# Prototype1.net
KiCad netlist of a schematic drawn in EAGLE
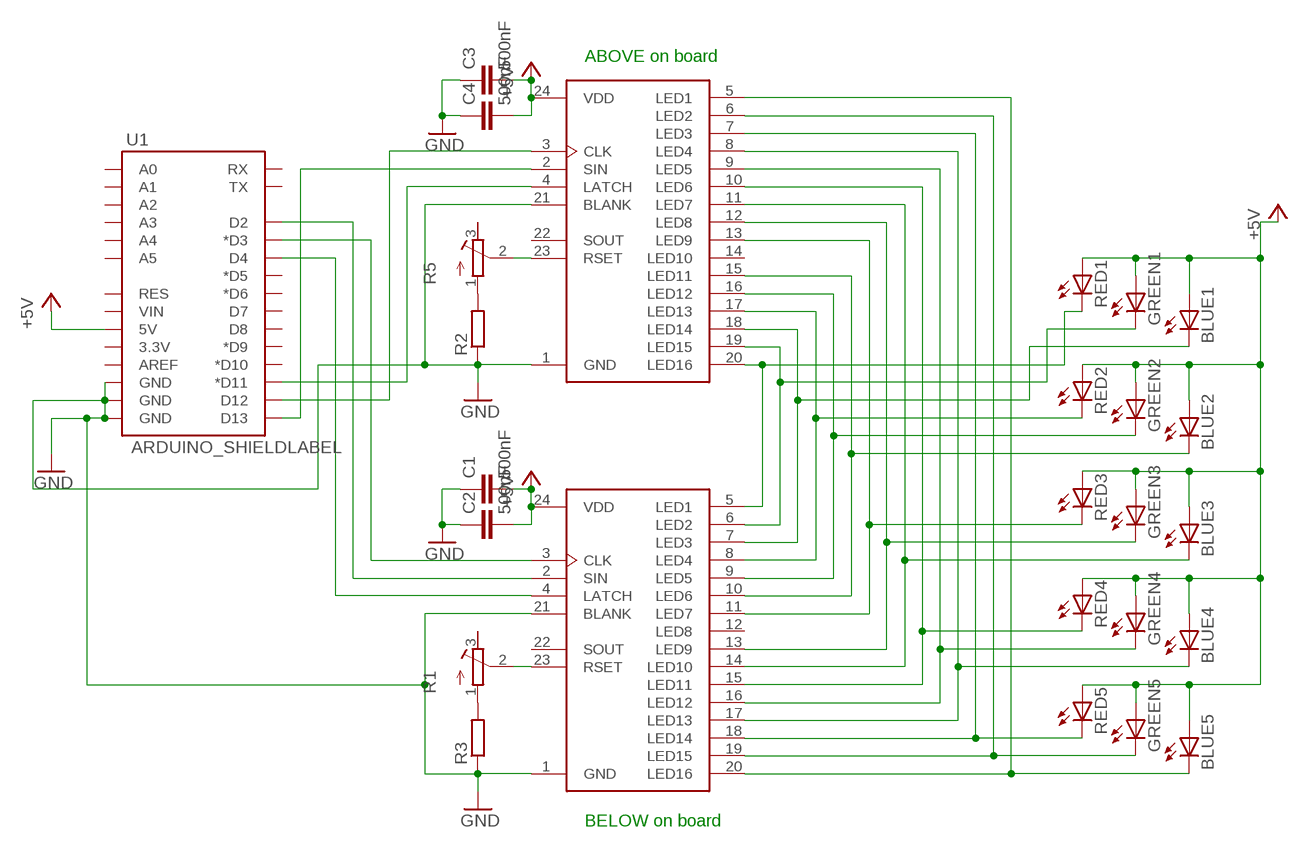
[diagram p0: schematic, sheet 1]

(export (version "E")
  (design (tool "Eeschema 10.0.6"))
  (components
    (comp (ref "BLUE1")
      (value "LEDKA-3528ASYC")
      (footprint "eagle-import:KA-3528ASYC")
      (libsource (lib "eagle-import") (part "LEDKA-3528ASYC"))
    )
    (comp (ref "BLUE2")
      (value "LEDKA-3528ASYC")
      (footprint "eagle-import:KA-3528ASYC")
      (libsource (lib "eagle-import") (part "LEDKA-3528ASYC"))
    )
    (comp (ref "BLUE3")
      (value "LEDKA-3528ASYC")
      (footprint "eagle-import:KA-3528ASYC")
      (libsource (lib "eagle-import") (part "LEDKA-3528ASYC"))
    )
    (comp (ref "BLUE4")
      (value "LEDKA-3528ASYC")
      (footprint "eagle-import:KA-3528ASYC")
      (libsource (lib "eagle-import") (part "LEDKA-3528ASYC"))
    )
    (comp (ref "BLUE5")
      (value "LEDKA-3528ASYC")
      (footprint "eagle-import:KA-3528ASYC")
      (libsource (lib "eagle-import") (part "LEDKA-3528ASYC"))
    )
    (comp (ref "C1")
      (value "500nF")
      (footprint "eagle-import:CAP-PTH-SMALL")
      (libsource (lib "eagle-import") (part "CAPPTH"))
    )
    (comp (ref "C2")
      (value "500nF")
      (footprint "eagle-import:CAP-PTH-SMALL")
      (libsource (lib "eagle-import") (part "CAPPTH"))
    )
    (comp (ref "C3")
      (value "500nF")
      (footprint "eagle-import:CAP-PTH-SMALL")
      (libsource (lib "eagle-import") (part "CAPPTH"))
    )
    (comp (ref "C4")
      (value "500nF")
      (footprint "eagle-import:CAP-PTH-SMALL")
      (libsource (lib "eagle-import") (part "CAPPTH"))
    )
    (comp (ref "GREEN1")
      (value "LEDKA-3528ASYC")
      (footprint "eagle-import:KA-3528ASYC")
      (libsource (lib "eagle-import") (part "LEDKA-3528ASYC"))
    )
    (comp (ref "GREEN2")
      (value "LEDKA-3528ASYC")
      (footprint "eagle-import:KA-3528ASYC")
      (libsource (lib "eagle-import") (part "LEDKA-3528ASYC"))
    )
    (comp (ref "GREEN3")
      (value "LEDKA-3528ASYC")
      (footprint "eagle-import:KA-3528ASYC")
      (libsource (lib "eagle-import") (part "LEDKA-3528ASYC"))
    )
    (comp (ref "GREEN4")
      (value "LEDKA-3528ASYC")
      (footprint "eagle-import:KA-3528ASYC")
      (libsource (lib "eagle-import") (part "LEDKA-3528ASYC"))
    )
    (comp (ref "GREEN5")
      (value "LEDKA-3528ASYC")
      (footprint "eagle-import:KA-3528ASYC")
      (libsource (lib "eagle-import") (part "LEDKA-3528ASYC"))
    )
    (comp (ref "R1")
      (value "R-TRIMM3165W")
      (footprint "eagle-import:RTRIM3165W")
      (libsource (lib "eagle-import") (part "R-TRIMM3165W"))
    )
    (comp (ref "R2")
      (value "R-EU_0204/7")
      (footprint "eagle-import:0204_7")
      (libsource (lib "eagle-import") (part "R-EU_0204/7"))
    )
    (comp (ref "R3")
      (value "R-EU_0204/7")
      (footprint "eagle-import:0204_7")
      (libsource (lib "eagle-import") (part "R-EU_0204/7"))
    )
    (comp (ref "R5")
      (value "R-TRIMM3165W")
      (footprint "eagle-import:RTRIM3165W")
      (libsource (lib "eagle-import") (part "R-TRIMM3165W"))
    )
    (comp (ref "RED1")
      (value "LEDSML0805")
      (footprint "eagle-import:SML0805")
      (libsource (lib "eagle-import") (part "LEDSML0805"))
    )
    (comp (ref "RED2")
      (value "LEDSML0805")
      (footprint "eagle-import:SML0805")
      (libsource (lib "eagle-import") (part "LEDSML0805"))
    )
    (comp (ref "RED3")
      (value "LEDSML0805")
      (footprint "eagle-import:SML0805")
      (libsource (lib "eagle-import") (part "LEDSML0805"))
    )
    (comp (ref "RED4")
      (value "LEDSML0805")
      (footprint "eagle-import:SML0805")
      (libsource (lib "eagle-import") (part "LEDSML0805"))
    )
    (comp (ref "RED5")
      (value "LEDSML0805")
      (footprint "eagle-import:SML0805")
      (libsource (lib "eagle-import") (part "LEDSML0805"))
    )
    (comp (ref "U$2")
      (value "CAT4016")
      (footprint "eagle-import:SOIC24W")
      (libsource (lib "eagle-import") (part "CAT4016"))
    )
    (comp (ref "U$3")
      (value "CAT4016")
      (footprint "eagle-import:SOIC24W")
      (libsource (lib "eagle-import") (part "CAT4016"))
    )
    (comp (ref "U1")
      (value "ARDUINO_SHIELDLABEL")
      (footprint "eagle-import:DUEMILANOVE_SHIELD")
      (libsource (lib "eagle-import") (part "ARDUINO_SHIELDLABEL"))
    )
  )
  (nets
    (net (code "1") (name "+5V") (class "Default")
      (node (ref "BLUE1") (pin "A") (pinfunction "A_A") (pintype "passive"))
      (node (ref "BLUE2") (pin "A") (pinfunction "A_A") (pintype "passive"))
      (node (ref "BLUE3") (pin "A") (pinfunction "A_A") (pintype "passive"))
      (node (ref "BLUE4") (pin "A") (pinfunction "A_A") (pintype "passive"))
      (node (ref "BLUE5") (pin "A") (pinfunction "A_A") (pintype "passive"))
      (node (ref "C1") (pin "2") (pinfunction "2_2") (pintype "passive"))
      (node (ref "C2") (pin "2") (pinfunction "2_2") (pintype "passive"))
      (node (ref "C3") (pin "2") (pinfunction "2_2") (pintype "passive"))
      (node (ref "C4") (pin "2") (pinfunction "2_2") (pintype "passive"))
      (node (ref "GREEN1") (pin "A") (pinfunction "A_A") (pintype "passive"))
      (node (ref "GREEN2") (pin "A") (pinfunction "A_A") (pintype "passive"))
      (node (ref "GREEN3") (pin "A") (pinfunction "A_A") (pintype "passive"))
      (node (ref "GREEN4") (pin "A") (pinfunction "A_A") (pintype "passive"))
      (node (ref "GREEN5") (pin "A") (pinfunction "A_A") (pintype "passive"))
      (node (ref "RED1") (pin "A") (pinfunction "A_A") (pintype "passive"))
      (node (ref "RED2") (pin "A") (pinfunction "A_A") (pintype "passive"))
      (node (ref "RED3") (pin "A") (pinfunction "A_A") (pintype "passive"))
      (node (ref "RED4") (pin "A") (pinfunction "A_A") (pintype "passive"))
      (node (ref "RED5") (pin "A") (pinfunction "A_A") (pintype "passive"))
      (node (ref "U$2") (pin "24") (pinfunction "VDD_24") (pintype "bidirectional"))
      (node (ref "U$3") (pin "24") (pinfunction "VDD_24") (pintype "bidirectional"))
      (node (ref "U1") (pin "5V") (pinfunction "5V_5V") (pintype "bidirectional"))
    )
    (net (code "2") (name "GND") (class "Default")
      (node (ref "C1") (pin "1") (pinfunction "1_1") (pintype "passive"))
      (node (ref "C2") (pin "1") (pinfunction "1_1") (pintype "passive"))
      (node (ref "C3") (pin "1") (pinfunction "1_1") (pintype "passive"))
      (node (ref "C4") (pin "1") (pinfunction "1_1") (pintype "passive"))
      (node (ref "R2") (pin "1") (pinfunction "1_1") (pintype "passive"))
      (node (ref "R3") (pin "1") (pinfunction "1_1") (pintype "passive"))
      (node (ref "U$2") (pin "1") (pinfunction "GND_1") (pintype "bidirectional"))
      (node (ref "U$2") (pin "21") (pinfunction "BLANK_21") (pintype "bidirectional"))
      (node (ref "U$3") (pin "1") (pinfunction "GND_1") (pintype "bidirectional"))
      (node (ref "U$3") (pin "21") (pinfunction "BLANK_21") (pintype "bidirectional"))
      (node (ref "U1") (pin "GND@0") (pinfunction "GND_GND@0") (pintype "bidirectional"))
      (node (ref "U1") (pin "GND@1") (pinfunction "GND_GND@1") (pintype "bidirectional"))
      (node (ref "U1") (pin "GND@2") (pinfunction "GND_GND@2") (pintype "bidirectional"))
    )
    (net (code "3") (name "Net-(R1-A)") (class "Default")
      (node (ref "R1") (pin "1") (pinfunction "A_1") (pintype "passive"))
      (node (ref "R3") (pin "2") (pinfunction "2_2") (pintype "passive"))
    )
    (net (code "4") (name "Net-(R1-S)") (class "Default")
      (node (ref "R1") (pin "2") (pinfunction "S_2") (pintype "passive"))
      (node (ref "U$2") (pin "23") (pinfunction "RSET_23") (pintype "bidirectional"))
    )
    (net (code "5") (name "Net-(R5-A)") (class "Default")
      (node (ref "R2") (pin "2") (pinfunction "2_2") (pintype "passive"))
      (node (ref "R5") (pin "1") (pinfunction "A_1") (pintype "passive"))
    )
    (net (code "6") (name "Net-(R5-S)") (class "Default")
      (node (ref "R5") (pin "2") (pinfunction "S_2") (pintype "passive"))
      (node (ref "U$3") (pin "23") (pinfunction "RSET_23") (pintype "bidirectional"))
    )
    (net (code "7") (name "Net-(U$2-CLK)") (class "Default")
      (node (ref "U$2") (pin "3") (pinfunction "CLK_3") (pintype "bidirectional"))
      (node (ref "U1") (pin "D3") (pinfunction "*D3_D3") (pintype "bidirectional"))
    )
    (net (code "8") (name "Net-(U$2-LATCH)") (class "Default")
      (node (ref "U$2") (pin "4") (pinfunction "LATCH_4") (pintype "bidirectional"))
      (node (ref "U1") (pin "D4") (pinfunction "D4_D4") (pintype "bidirectional"))
    )
    (net (code "9") (name "Net-(U$2-LED1)") (class "Default")
      (node (ref "RED1") (pin "C") (pinfunction "C_C") (pintype "passive"))
      (node (ref "U$2") (pin "5") (pinfunction "LED1_5") (pintype "bidirectional"))
      (node (ref "U$3") (pin "20") (pinfunction "LED16_20") (pintype "bidirectional"))
    )
    (net (code "10") (name "Net-(U$2-LED2)") (class "Default")
      (node (ref "GREEN1") (pin "C") (pinfunction "C_C") (pintype "passive"))
      (node (ref "U$2") (pin "6") (pinfunction "LED2_6") (pintype "bidirectional"))
      (node (ref "U$3") (pin "19") (pinfunction "LED15_19") (pintype "bidirectional"))
    )
    (net (code "11") (name "Net-(U$2-LED3)") (class "Default")
      (node (ref "BLUE1") (pin "C") (pinfunction "C_C") (pintype "passive"))
      (node (ref "U$2") (pin "7") (pinfunction "LED3_7") (pintype "bidirectional"))
      (node (ref "U$3") (pin "18") (pinfunction "LED14_18") (pintype "bidirectional"))
    )
    (net (code "12") (name "Net-(U$2-LED4)") (class "Default")
      (node (ref "RED2") (pin "C") (pinfunction "C_C") (pintype "passive"))
      (node (ref "U$2") (pin "8") (pinfunction "LED4_8") (pintype "bidirectional"))
      (node (ref "U$3") (pin "17") (pinfunction "LED13_17") (pintype "bidirectional"))
    )
    (net (code "13") (name "Net-(U$2-LED5)") (class "Default")
      (node (ref "GREEN2") (pin "C") (pinfunction "C_C") (pintype "passive"))
      (node (ref "U$2") (pin "9") (pinfunction "LED5_9") (pintype "bidirectional"))
      (node (ref "U$3") (pin "16") (pinfunction "LED12_16") (pintype "bidirectional"))
    )
    (net (code "14") (name "Net-(U$2-LED6)") (class "Default")
      (node (ref "BLUE2") (pin "C") (pinfunction "C_C") (pintype "passive"))
      (node (ref "U$2") (pin "10") (pinfunction "LED6_10") (pintype "bidirectional"))
      (node (ref "U$3") (pin "15") (pinfunction "LED11_15") (pintype "bidirectional"))
    )
    (net (code "15") (name "Net-(U$2-LED7)") (class "Default")
      (node (ref "RED3") (pin "C") (pinfunction "C_C") (pintype "passive"))
      (node (ref "U$2") (pin "11") (pinfunction "LED7_11") (pintype "bidirectional"))
      (node (ref "U$3") (pin "13") (pinfunction "LED9_13") (pintype "bidirectional"))
    )
    (net (code "16") (name "Net-(U$2-LED9)") (class "Default")
      (node (ref "GREEN3") (pin "C") (pinfunction "C_C") (pintype "passive"))
      (node (ref "U$2") (pin "13") (pinfunction "LED9_13") (pintype "bidirectional"))
      (node (ref "U$3") (pin "12") (pinfunction "LED8_12") (pintype "bidirectional"))
    )
    (net (code "17") (name "Net-(U$2-LED10)") (class "Default")
      (node (ref "BLUE3") (pin "C") (pinfunction "C_C") (pintype "passive"))
      (node (ref "U$2") (pin "14") (pinfunction "LED10_14") (pintype "bidirectional"))
      (node (ref "U$3") (pin "11") (pinfunction "LED7_11") (pintype "bidirectional"))
    )
    (net (code "18") (name "Net-(U$2-LED11)") (class "Default")
      (node (ref "RED4") (pin "C") (pinfunction "C_C") (pintype "passive"))
      (node (ref "U$2") (pin "15") (pinfunction "LED11_15") (pintype "bidirectional"))
      (node (ref "U$3") (pin "10") (pinfunction "LED6_10") (pintype "bidirectional"))
    )
    (net (code "19") (name "Net-(U$2-LED12)") (class "Default")
      (node (ref "GREEN4") (pin "C") (pinfunction "C_C") (pintype "passive"))
      (node (ref "U$2") (pin "16") (pinfunction "LED12_16") (pintype "bidirectional"))
      (node (ref "U$3") (pin "9") (pinfunction "LED5_9") (pintype "bidirectional"))
    )
    (net (code "20") (name "Net-(U$2-LED13)") (class "Default")
      (node (ref "BLUE4") (pin "C") (pinfunction "C_C") (pintype "passive"))
      (node (ref "U$2") (pin "17") (pinfunction "LED13_17") (pintype "bidirectional"))
      (node (ref "U$3") (pin "8") (pinfunction "LED4_8") (pintype "bidirectional"))
    )
    (net (code "21") (name "Net-(U$2-LED14)") (class "Default")
      (node (ref "RED5") (pin "C") (pinfunction "C_C") (pintype "passive"))
      (node (ref "U$2") (pin "18") (pinfunction "LED14_18") (pintype "bidirectional"))
      (node (ref "U$3") (pin "7") (pinfunction "LED3_7") (pintype "bidirectional"))
    )
    (net (code "22") (name "Net-(U$2-LED15)") (class "Default")
      (node (ref "GREEN5") (pin "C") (pinfunction "C_C") (pintype "passive"))
      (node (ref "U$2") (pin "19") (pinfunction "LED15_19") (pintype "bidirectional"))
      (node (ref "U$3") (pin "6") (pinfunction "LED2_6") (pintype "bidirectional"))
    )
    (net (code "23") (name "Net-(U$2-LED16)") (class "Default")
      (node (ref "BLUE5") (pin "C") (pinfunction "C_C") (pintype "passive"))
      (node (ref "U$2") (pin "20") (pinfunction "LED16_20") (pintype "bidirectional"))
      (node (ref "U$3") (pin "5") (pinfunction "LED1_5") (pintype "bidirectional"))
    )
    (net (code "24") (name "Net-(U$2-SIN)") (class "Default")
      (node (ref "U$2") (pin "2") (pinfunction "SIN_2") (pintype "bidirectional"))
      (node (ref "U1") (pin "D2") (pinfunction "D2_D2") (pintype "bidirectional"))
    )
    (net (code "25") (name "Net-(U$3-CLK)") (class "Default")
      (node (ref "U$3") (pin "3") (pinfunction "CLK_3") (pintype "bidirectional"))
      (node (ref "U1") (pin "D12") (pinfunction "D12_D12") (pintype "bidirectional"))
    )
    (net (code "26") (name "Net-(U$3-LATCH)") (class "Default")
      (node (ref "U$3") (pin "4") (pinfunction "LATCH_4") (pintype "bidirectional"))
      (node (ref "U1") (pin "D11") (pinfunction "*D11_D11") (pintype "bidirectional"))
    )
    (net (code "27") (name "Net-(U$3-SIN)") (class "Default")
      (node (ref "U$3") (pin "2") (pinfunction "SIN_2") (pintype "bidirectional"))
      (node (ref "U1") (pin "D13") (pinfunction "D13_D13") (pintype "bidirectional"))
    )
    (net (code "28") (name "unconnected-(R1-E-Pad3)") (class "Default")
      (node (ref "R1") (pin "3") (pinfunction "E_3") (pintype "passive"))
    )
    (net (code "29") (name "unconnected-(R5-E-Pad3)") (class "Default")
      (node (ref "R5") (pin "3") (pinfunction "E_3") (pintype "passive"))
    )
    (net (code "30") (name "unconnected-(U$2-LED8-Pad12)") (class "Default")
      (node (ref "U$2") (pin "12") (pinfunction "LED8_12") (pintype "bidirectional"))
    )
    (net (code "31") (name "unconnected-(U$2-SOUT-Pad22)") (class "Default")
      (node (ref "U$2") (pin "22") (pinfunction "SOUT_22") (pintype "bidirectional"))
    )
    (net (code "32") (name "unconnected-(U$3-LED10-Pad14)") (class "Default")
      (node (ref "U$3") (pin "14") (pinfunction "LED10_14") (pintype "bidirectional"))
    )
    (net (code "33") (name "unconnected-(U$3-SOUT-Pad22)") (class "Default")
      (node (ref "U$3") (pin "22") (pinfunction "SOUT_22") (pintype "bidirectional"))
    )
    (net (code "34") (name "unconnected-(U1-*D5-PadD5)") (class "Default")
      (node (ref "U1") (pin "D5") (pinfunction "*D5_D5") (pintype "bidirectional"))
    )
    (net (code "35") (name "unconnected-(U1-*D6-PadD6)") (class "Default")
      (node (ref "U1") (pin "D6") (pinfunction "*D6_D6") (pintype "bidirectional"))
    )
    (net (code "36") (name "unconnected-(U1-*D9-PadD9)") (class "Default")
      (node (ref "U1") (pin "D9") (pinfunction "*D9_D9") (pintype "bidirectional"))
    )
    (net (code "37") (name "unconnected-(U1-*D10-PadD10)") (class "Default")
      (node (ref "U1") (pin "D10") (pinfunction "*D10_D10") (pintype "bidirectional"))
    )
    (net (code "38") (name "unconnected-(U1-Pad3.3V)") (class "Default")
      (node (ref "U1") (pin "3.3V") (pinfunction "3.3V_3.3V") (pintype "bidirectional"))
    )
    (net (code "39") (name "unconnected-(U1-PadA0)") (class "Default")
      (node (ref "U1") (pin "A0") (pinfunction "A0_A0") (pintype "bidirectional"))
    )
    (net (code "40") (name "unconnected-(U1-PadA1)") (class "Default")
      (node (ref "U1") (pin "A1") (pinfunction "A1_A1") (pintype "bidirectional"))
    )
    (net (code "41") (name "unconnected-(U1-PadA2)") (class "Default")
      (node (ref "U1") (pin "A2") (pinfunction "A2_A2") (pintype "bidirectional"))
    )
    (net (code "42") (name "unconnected-(U1-PadA3)") (class "Default")
      (node (ref "U1") (pin "A3") (pinfunction "A3_A3") (pintype "bidirectional"))
    )
    (net (code "43") (name "unconnected-(U1-PadA4)") (class "Default")
      (node (ref "U1") (pin "A4") (pinfunction "A4_A4") (pintype "bidirectional"))
    )
    (net (code "44") (name "unconnected-(U1-PadA5)") (class "Default")
      (node (ref "U1") (pin "A5") (pinfunction "A5_A5") (pintype "bidirectional"))
    )
    (net (code "45") (name "unconnected-(U1-PadAREF)") (class "Default")
      (node (ref "U1") (pin "AREF") (pinfunction "AREF_AREF") (pintype "bidirectional"))
    )
    (net (code "46") (name "unconnected-(U1-PadD7)") (class "Default")
      (node (ref "U1") (pin "D7") (pinfunction "D7_D7") (pintype "bidirectional"))
    )
    (net (code "47") (name "unconnected-(U1-PadD8)") (class "Default")
      (node (ref "U1") (pin "D8") (pinfunction "D8_D8") (pintype "bidirectional"))
    )
    (net (code "48") (name "unconnected-(U1-PadRES)") (class "Default")
      (node (ref "U1") (pin "RES") (pinfunction "RES_RES") (pintype "bidirectional"))
    )
    (net (code "49") (name "unconnected-(U1-PadRX)") (class "Default")
      (node (ref "U1") (pin "RX") (pinfunction "RX_RX") (pintype "bidirectional"))
    )
    (net (code "50") (name "unconnected-(U1-PadTX)") (class "Default")
      (node (ref "U1") (pin "TX") (pinfunction "TX_TX") (pintype "bidirectional"))
    )
    (net (code "51") (name "unconnected-(U1-PadVIN)") (class "Default")
      (node (ref "U1") (pin "VIN") (pinfunction "VIN_VIN") (pintype "bidirectional"))
    )
  )
)
